# STM32WLE5CBU6_dev_board.net
KiCad netlist of a schematic drawn in Altium Designer
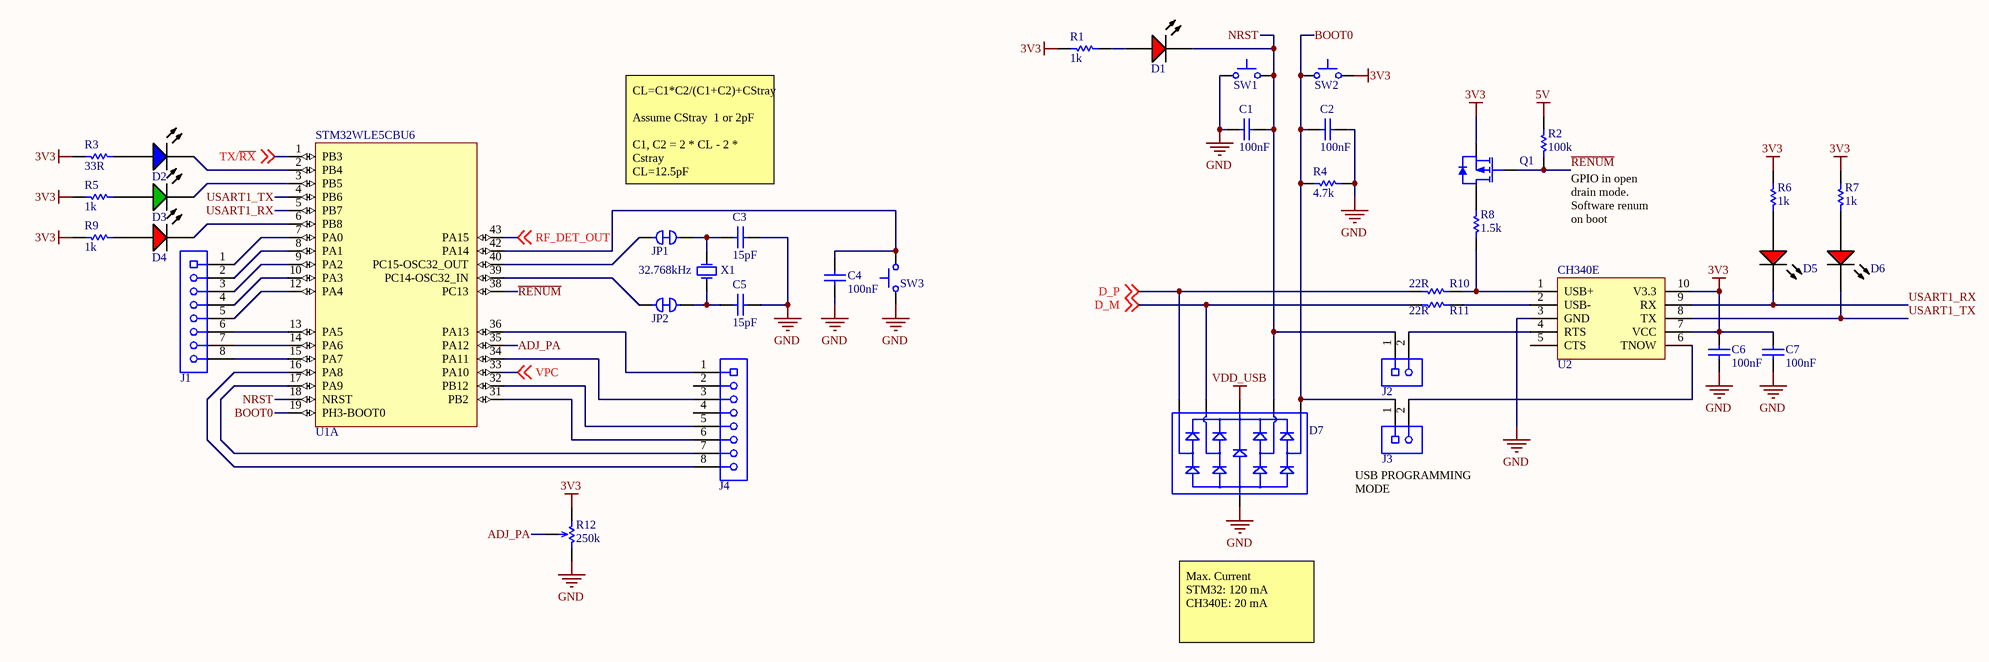
[diagram p0: STM32WLE5CBU6 dev board.SchDoc]

(export (version "E")
  (design (tool "Eeschema 10.0.6"))
  (components
    (comp (ref "C1")
      (value "100nF")
      (footprint "CAPC1608X10N")
      (description "Cap Ceramic 0.1uF 50V X7R 20% SMD 0603 125C T/R")
      (fields (field (name "TOLERANCE") "20%") (field (name "Comment") "C0603C104M5RACTU"))
      (libsource (lib "UWA Aerospace") (part "C0603C104M5RACTU"))
    )
    (comp (ref "C2")
      (value "100nF")
      (footprint "CAPC1608X10N")
      (description "Cap Ceramic 0.1uF 50V X7R 20% SMD 0603 125C T/R")
      (fields (field (name "TOLERANCE") "20%") (field (name "Comment") "C0603C104M5RACTU"))
      (libsource (lib "UWA Aerospace") (part "C0603C104M5RACTU"))
    )
    (comp (ref "C3")
      (value "15pF")
      (footprint "CAPC1005X05N")
      (description "CAP CER 15PF 50V C0G/NP0 0402")
      (fields (field (name "VOLTAGE") "50V") (field (name "TOLERANCE") "5%"))
      (libsource (lib "UWA Aerospace") (part "C0603C104M5RACTU"))
    )
    (comp (ref "C4")
      (value "100nF")
      (footprint "CAPC1608X10N")
      (description "Cap Ceramic 0.1uF 50V X7R 20% SMD 0603 125C T/R")
      (fields (field (name "TOLERANCE") "20%") (field (name "Comment") "C0603C104M5RACTU"))
      (libsource (lib "UWA Aerospace") (part "C0603C104M5RACTU"))
    )
    (comp (ref "C5")
      (value "15pF")
      (footprint "CAPC1005X05N")
      (description "CAP CER 15PF 50V C0G/NP0 0402")
      (fields (field (name "VOLTAGE") "50V") (field (name "TOLERANCE") "5%"))
      (libsource (lib "UWA Aerospace") (part "C0603C104M5RACTU"))
    )
    (comp (ref "C6")
      (value "100nF")
      (footprint "CAPC1608X10N")
      (description "Cap Ceramic 0.1uF 50V X7R 20% SMD 0603 125C T/R")
      (fields (field (name "TOLERANCE") "20%") (field (name "Comment") "C0603C104M5RACTU"))
      (libsource (lib "UWA Aerospace") (part "C0603C104M5RACTU"))
    )
    (comp (ref "C7")
      (value "100nF")
      (footprint "CAPC1608X10N")
      (description "Cap Ceramic 0.1uF 50V X7R 20% SMD 0603 125C T/R")
      (fields (field (name "TOLERANCE") "20%") (field (name "Comment") "C0603C104M5RACTU"))
      (libsource (lib "UWA Aerospace") (part "C0603C104M5RACTU"))
    )
    (comp (ref "D1")
      (value "150060RS75000")
      (footprint "0603_A")
      (description "LED Low-Power Uni-Color Red 630nm 2V 2-Pin Chip 0603(1608Metric) T/R")
      (libsource (lib "UWA Aerospace") (part "LED - Red"))
    )
    (comp (ref "D2")
      (value "LTST-C191TBKT")
      (footprint "FP-150060GS75000-MFG")
      (description "LED BLUE CLEAR 0603 SMD")
      (libsource (lib "UWA Aerospace") (part "LED - Blue"))
    )
    (comp (ref "D3")
      (value "150060GS75000")
      (footprint "FP-150060GS75000-MFG")
      (description "Led, Green, 520 Nm, 3.2 V, 30 Ma, 430 Mcd Rohs Compliant: Yes")
      (libsource (lib "UWA Aerospace") (part "LED - Green"))
    )
    (comp (ref "D4")
      (value "150060RS75000")
      (footprint "0603_A")
      (description "LED Low-Power Uni-Color Red 630nm 2V 2-Pin Chip 0603(1608Metric) T/R")
      (libsource (lib "UWA Aerospace") (part "LED - Red"))
    )
    (comp (ref "D5")
      (value "150060RS75000")
      (footprint "0603_A")
      (description "LED Low-Power Uni-Color Red 630nm 2V 2-Pin Chip 0603(1608Metric) T/R")
      (libsource (lib "UWA Aerospace") (part "LED - Red"))
    )
    (comp (ref "D6")
      (value "150060RS75000")
      (footprint "0603_A")
      (description "LED Low-Power Uni-Color Red 630nm 2V 2-Pin Chip 0603(1608Metric) T/R")
      (libsource (lib "UWA Aerospace") (part "LED - Red"))
    )
    (comp (ref "D7")
      (value "SRV05-4-P-T7")
      (footprint "SOT95P280X145-6N")
      (description "SRV05 Series 4 Ch 3.5 pF 15 Vclamp Steering Diode/TVS Array Combo - SOT-23-6 USB ESD")
      (libsource (lib "UWA Aerospace") (part "Diode - USB Clamp (Dual USB)"))
    )
    (comp (ref "J1")
      (value "22-28-4080")
      (footprint "22-28-4080-Footprint-1")
      (description "Conn Unshrouded Header HDR 8 POS 2.54mm Solder ST Thru-Hole Bag")
      (libsource (lib "") (part "Connector - 1x8 Single Sided_1"))
    )
    (comp (ref "J2")
      (value "22-28-4020")
      (footprint "22-28-4020-Footprint-1")
      (description "KK 254 Breakaway Header, Vertical, 2 Circuits, Tin (Sn) Plating, Mating Pin Length 6.09mm 2 POS")
      (libsource (lib "UWA Aerospace") (part "22-28-4020"))
    )
    (comp (ref "J3")
      (value "22-28-4020")
      (footprint "22-28-4020-Footprint-1")
      (description "KK 254 Breakaway Header, Vertical, 2 Circuits, Tin (Sn) Plating, Mating Pin Length 6.09mm 2 POS")
      (libsource (lib "UWA Aerospace") (part "22-28-4020"))
    )
    (comp (ref "J4")
      (value "22-28-4080")
      (footprint "22-28-4080-Footprint-1")
      (description "Conn Unshrouded Header HDR 8 POS 2.54mm Solder ST Thru-Hole Bag")
      (libsource (lib "UWA Aerospace") (part "Connector - 1x8 Single Sided"))
    )
    (comp (ref "JP1")
      (value "RC0603FR-070RL")
      (footprint "RESC1608X05N")
      (description "RC Series 0603 0.1 W 0 Ohm Jumper Surface Mount Thick Film Chip Resistor")
      (fields (field (name "TOLERANCE") "1%"))
      (libsource (lib "UWA Aerospace") (part "Jumper - Closed"))
    )
    (comp (ref "JP2")
      (value "RC0603FR-070RL")
      (footprint "RESC1608X05N")
      (description "RC Series 0603 0.1 W 0 Ohm Jumper Surface Mount Thick Film Chip Resistor")
      (fields (field (name "TOLERANCE") "1%"))
      (libsource (lib "UWA Aerospace") (part "Jumper - Closed"))
    )
    (comp (ref "Q1")
      (value "SI2301CDS-T1-GE3")
      (footprint "SOT95P237X112-3N")
      (description "Trans Mosfet P-ch 20V 3.1A 3-PIN SOT-23 T/r / Mosfet P-ch 20V 3.1A SOT23-3")
      (libsource (lib "UWA Aerospace") (part "Transistor - MOSFET P-Channel"))
    )
    (comp (ref "R1")
      (value "1k")
      (footprint "RESC1608X05N")
      (description "Res Thick Film 0603 1K Ohm 1% 1/10W ±100ppm/°C Molded SMD SMD Paper T/R")
      (fields (field (name "TOLERANCE") "1%") (field (name "Comment") "RC0603FR-071KL"))
      (libsource (lib "UWA Aerospace") (part "Resistor"))
    )
    (comp (ref "R2")
      (value "100k")
      (footprint "RESC1608X05N")
      (description "RES SMD 100K OHM 1% 1/10W 0603")
      (fields (field (name "TOLERANCE") "1%") (field (name "Comment") "RC0603FR-07100KL"))
      (libsource (lib "UWA Aerospace") (part "Resistor"))
    )
    (comp (ref "R3")
      (value "33R")
      (footprint "RESC1608X05N")
      (description "Res Thick Film 0603 33 Ohm 1% 1/10W ±100ppm/°C Molded SMD Paper T/R")
      (fields (field (name "TOLERANCE") "1%") (field (name "Comment") "CRCW060333R0FKEAC"))
      (libsource (lib "UWA Aerospace") (part "Resistor"))
    )
    (comp (ref "R4")
      (value "CRCW06034K70FKEAC")
      (footprint "RESC1608X05N")
      (description "4.7kO 1% 0603 thick film")
      (fields (field (name "RESISTANCE") "4.7k") (field (name "TOLERANCE") "1%"))
      (libsource (lib "UWA Aerospace") (part "WSL2010R0100FEA18"))
    )
    (comp (ref "R5")
      (value "1k")
      (footprint "RESC1608X05N")
      (description "Res Thick Film 0603 1K Ohm 1% 1/10W ±100ppm/°C Molded SMD SMD Paper T/R")
      (fields (field (name "TOLERANCE") "1%") (field (name "Comment") "RC0603FR-071KL"))
      (libsource (lib "UWA Aerospace") (part "Resistor"))
    )
    (comp (ref "R6")
      (value "1k")
      (footprint "RESC1608X05N")
      (description "Res Thick Film 0603 1K Ohm 1% 1/10W ±100ppm/°C Molded SMD SMD Paper T/R")
      (fields (field (name "TOLERANCE") "1%") (field (name "Comment") "RC0603FR-071KL"))
      (libsource (lib "UWA Aerospace") (part "Resistor"))
    )
    (comp (ref "R7")
      (value "1k")
      (footprint "RESC1608X05N")
      (description "Res Thick Film 0603 1K Ohm 1% 1/10W ±100ppm/°C Molded SMD SMD Paper T/R")
      (fields (field (name "TOLERANCE") "1%") (field (name "Comment") "RC0603FR-071KL"))
      (libsource (lib "UWA Aerospace") (part "Resistor"))
    )
    (comp (ref "R8")
      (value "1.5k")
      (footprint "RESC1608X05N")
      (description "Res Thick Film 0603 1.5K Ohm 5% 0.1W(1/10W) ±200ppm/C Pad SMD Automotive T/R")
      (fields (field (name "TOLERANCE") "5%") (field (name "Comment") "RK73B1JTTD152J"))
      (libsource (lib "UWA Aerospace") (part "Resistor"))
    )
    (comp (ref "R9")
      (value "1k")
      (footprint "RESC1608X05N")
      (description "Res Thick Film 0603 1K Ohm 1% 1/10W ±100ppm/°C Molded SMD SMD Paper T/R")
      (fields (field (name "TOLERANCE") "1%") (field (name "Comment") "RC0603FR-071KL"))
      (libsource (lib "UWA Aerospace") (part "Resistor"))
    )
    (comp (ref "R10")
      (value "22R")
      (footprint "RESC1005X04N")
      (description "22R 1/16W %1 0402")
      (fields (field (name "TOLERANCE") "±1%") (field (name "Comment") "0402WGF220JTCE"))
      (libsource (lib "UWA Aerospace") (part "Resistor"))
    )
    (comp (ref "R11")
      (value "22R")
      (footprint "RESC1005X04N")
      (description "22R 1/16W %1 0402")
      (fields (field (name "TOLERANCE") "±1%") (field (name "Comment") "0402WGF220JTCE"))
      (libsource (lib "UWA Aerospace") (part "Resistor"))
    )
    (comp (ref "R12")
      (value "250k")
      (footprint "3362P-1-502LF-Footprint-1")
      (description "Bourns 3362P-1-254LF THT Trimpot, 250k, 10%, 1 Turn")
      (fields (field (name "TOLERANCE") "10%") (field (name "Comment") "3362P-1-254LF"))
      (libsource (lib "UWA Aerospace") (part "3362F-1-254LF"))
    )
    (comp (ref "SW1")
      (value "TL3342F160QG")
      (footprint "ESWI-TL3342F160QG_V")
      (description "Switch Tactile N.O. SPST Round Button Gull Wing 0.05A 12VDC 100000Cycles 1.57N SMD T/R")
      (libsource (lib "UWA Aerospace") (part "Switch - Tactile"))
    )
    (comp (ref "SW2")
      (value "TL3342F160QG")
      (footprint "ESWI-TL3342F160QG_V")
      (description "Switch Tactile N.O. SPST Round Button Gull Wing 0.05A 12VDC 100000Cycles 1.57N SMD T/R")
      (libsource (lib "UWA Aerospace") (part "Switch - Tactile"))
    )
    (comp (ref "SW3")
      (value "TL3342F160QG")
      (footprint "ESWI-TL3342F160QG_V")
      (description "Switch Tactile N.O. SPST Round Button Gull Wing 0.05A 12VDC 100000Cycles 1.57N SMD T/R")
      (libsource (lib "UWA Aerospace") (part "Switch - Tactile"))
    )
    (comp (ref "U1")
      (value "STM32WLE5CBU6")
      (footprint "QFN50P700X700X60_HS-49L")
      (description "Microcontroller 32-Bit Arm Cortex-M4 RISC 128Kbyte 1.8V to 3.6V 48-Pin UFQFPN Industrial")
      (libsource (lib "UWA Aerospace") (part "STM32WLE5CBU6-Symbol-1"))
    )
    (comp (ref "U2")
      (value "CH340E")
      (footprint "TSSOP50P490X110-10N")
      (description "Transceiver 2Mbps USB 2.0 MSOP-10 USB ICs ROHS")
      (libsource (lib "UWA Aerospace") (part "CH340-Symbol-1"))
    )
    (comp (ref "X1")
      (value "32.768kHz")
      (footprint "Q13FC1350000400-Footprint-1")
      (description "Crystal 0.032768MHz ±20ppm (Tol) 12.5pF FUND 70000Ohm 2-Pin CSMD T/R 32.768 kHz")
      (fields (field (name "Comment") "Q13FC1350000400"))
      (libsource (lib "UWA Aerospace") (part "Crystal"))
    )
  )
  (nets
    (net (code "1") (name "/ADJ_PA") (class "Default")
      (node (ref "R12") (pin "2") (pinfunction "W_2") (pintype "passive"))
      (node (ref "U1") (pin "35") (pinfunction "PA12_35") (pintype "bidirectional"))
    )
    (net (code "2") (name "/BOOT0") (class "Default")
      (node (ref "C2") (pin "2") (pinfunction "2_2") (pintype "passive"))
      (node (ref "D7") (pin "6") (pinfunction "6_6") (pintype "passive"))
      (node (ref "J3") (pin "1") (pinfunction "1_1") (pintype "passive"))
      (node (ref "R4") (pin "2") (pinfunction "2_2") (pintype "passive"))
      (node (ref "SW2") (pin "1") (pinfunction "1_1") (pintype "passive"))
      (node (ref "U1") (pin "19") (pinfunction "PH3-BOOT0_19") (pintype "bidirectional"))
    )
    (net (code "3") (name "/NRST") (class "Default")
      (node (ref "C1") (pin "1") (pinfunction "1_1") (pintype "passive"))
      (node (ref "D1") (pin "2") (pinfunction "K_2") (pintype "passive"))
      (node (ref "D7") (pin "4") (pinfunction "4_4") (pintype "passive"))
      (node (ref "J2") (pin "1") (pinfunction "1_1") (pintype "passive"))
      (node (ref "SW1") (pin "2") (pinfunction "2_2") (pintype "passive"))
      (node (ref "U1") (pin "18") (pinfunction "NRST_18") (pintype "bidirectional"))
    )
    (net (code "4") (name "/USART1_RX") (class "Default")
      (node (ref "D5") (pin "2") (pinfunction "K_2") (pintype "passive"))
      (node (ref "U1") (pin "5") (pinfunction "PB7_5") (pintype "bidirectional"))
      (node (ref "U2") (pin "9") (pinfunction "RX_9") (pintype "passive"))
    )
    (net (code "5") (name "/USART1_TX") (class "Default")
      (node (ref "D6") (pin "2") (pinfunction "K_2") (pintype "passive"))
      (node (ref "U1") (pin "4") (pinfunction "PB6_4") (pintype "bidirectional"))
      (node (ref "U2") (pin "8") (pinfunction "TX_8") (pintype "passive"))
    )
    (net (code "6") (name "/~{RENUM}") (class "Default")
      (node (ref "Q1") (pin "1") (pinfunction "G_1") (pintype "passive"))
      (node (ref "R2") (pin "1") (pinfunction "1_1") (pintype "passive"))
      (node (ref "U1") (pin "38") (pinfunction "PC13_38") (pintype "bidirectional"))
    )
    (net (code "7") (name "3V3") (class "Default")
      (node (ref "C6") (pin "2") (pinfunction "2_2") (pintype "passive"))
      (node (ref "C7") (pin "2") (pinfunction "2_2") (pintype "passive"))
      (node (ref "Q1") (pin "2") (pinfunction "S_2") (pintype "passive"))
      (node (ref "R1") (pin "2") (pinfunction "2_2") (pintype "passive"))
      (node (ref "R12") (pin "1") (pinfunction "CCW_1") (pintype "passive"))
      (node (ref "R3") (pin "1") (pinfunction "1_1") (pintype "passive"))
      (node (ref "R5") (pin "2") (pinfunction "2_2") (pintype "passive"))
      (node (ref "R6") (pin "2") (pinfunction "2_2") (pintype "passive"))
      (node (ref "R7") (pin "2") (pinfunction "2_2") (pintype "passive"))
      (node (ref "R9") (pin "2") (pinfunction "2_2") (pintype "passive"))
      (node (ref "SW2") (pin "2") (pinfunction "2_2") (pintype "passive"))
      (node (ref "U2") (pin "10") (pinfunction "V3.3_10") (pintype "passive"))
      (node (ref "U2") (pin "7") (pinfunction "VCC_7") (pintype "passive"))
    )
    (net (code "8") (name "5V") (class "Default")
      (node (ref "R2") (pin "2") (pinfunction "2_2") (pintype "passive"))
    )
    (net (code "9") (name "D_M") (class "Default")
      (node (ref "D7") (pin "3") (pinfunction "3_3") (pintype "passive"))
      (node (ref "R11") (pin "1") (pinfunction "1_1") (pintype "passive"))
    )
    (net (code "10") (name "D_P") (class "Default")
      (node (ref "D7") (pin "1") (pinfunction "1_1") (pintype "passive"))
      (node (ref "R10") (pin "1") (pinfunction "1_1") (pintype "passive"))
    )
    (net (code "11") (name "GND") (class "Default")
      (node (ref "C1") (pin "2") (pinfunction "2_2") (pintype "passive"))
      (node (ref "C2") (pin "1") (pinfunction "1_1") (pintype "passive"))
      (node (ref "C3") (pin "1") (pinfunction "1_1") (pintype "passive"))
      (node (ref "C4") (pin "2") (pinfunction "2_2") (pintype "passive"))
      (node (ref "C5") (pin "1") (pinfunction "1_1") (pintype "passive"))
      (node (ref "C6") (pin "1") (pinfunction "1_1") (pintype "passive"))
      (node (ref "C7") (pin "1") (pinfunction "1_1") (pintype "passive"))
      (node (ref "D7") (pin "2") (pinfunction "2_2") (pintype "passive"))
      (node (ref "R12") (pin "3") (pinfunction "CW_3") (pintype "passive"))
      (node (ref "R4") (pin "1") (pinfunction "1_1") (pintype "passive"))
      (node (ref "SW1") (pin "1") (pinfunction "1_1") (pintype "passive"))
      (node (ref "SW3") (pin "1") (pinfunction "1_1") (pintype "passive"))
      (node (ref "U2") (pin "3") (pinfunction "GND_3") (pintype "passive"))
    )
    (net (code "12") (name "Net-(D1-A)") (class "Default")
      (node (ref "D1") (pin "1") (pinfunction "A_1") (pintype "passive"))
      (node (ref "R1") (pin "1") (pinfunction "1_1") (pintype "passive"))
    )
    (net (code "13") (name "Net-(D2-A)") (class "Default")
      (node (ref "D2") (pin "1") (pinfunction "A_1") (pintype "passive"))
      (node (ref "R3") (pin "2") (pinfunction "2_2") (pintype "passive"))
    )
    (net (code "14") (name "Net-(D2-K)") (class "Default")
      (node (ref "D2") (pin "2") (pinfunction "K_2") (pintype "passive"))
      (node (ref "U1") (pin "2") (pinfunction "PB4_2") (pintype "bidirectional"))
    )
    (net (code "15") (name "Net-(D3-A)") (class "Default")
      (node (ref "D3") (pin "1") (pinfunction "A_1") (pintype "passive"))
      (node (ref "R5") (pin "1") (pinfunction "1_1") (pintype "passive"))
    )
    (net (code "16") (name "Net-(D3-K)") (class "Default")
      (node (ref "D3") (pin "2") (pinfunction "K_2") (pintype "passive"))
      (node (ref "U1") (pin "3") (pinfunction "PB5_3") (pintype "bidirectional"))
    )
    (net (code "17") (name "Net-(D4-A)") (class "Default")
      (node (ref "D4") (pin "1") (pinfunction "A_1") (pintype "passive"))
      (node (ref "R9") (pin "1") (pinfunction "1_1") (pintype "passive"))
    )
    (net (code "18") (name "Net-(D4-K)") (class "Default")
      (node (ref "D4") (pin "2") (pinfunction "K_2") (pintype "passive"))
      (node (ref "U1") (pin "6") (pinfunction "PB8_6") (pintype "bidirectional"))
    )
    (net (code "19") (name "Net-(D5-A)") (class "Default")
      (node (ref "D5") (pin "1") (pinfunction "A_1") (pintype "passive"))
      (node (ref "R6") (pin "1") (pinfunction "1_1") (pintype "passive"))
    )
    (net (code "20") (name "Net-(D6-A)") (class "Default")
      (node (ref "D6") (pin "1") (pinfunction "A_1") (pintype "passive"))
      (node (ref "R7") (pin "1") (pinfunction "1_1") (pintype "passive"))
    )
    (net (code "21") (name "Net-(Q1-D)") (class "Default")
      (node (ref "Q1") (pin "3") (pinfunction "D_3") (pintype "passive"))
      (node (ref "R8") (pin "2") (pinfunction "2_2") (pintype "passive"))
    )
    (net (code "22") (name "Net-(U1A-PA0)") (class "Default")
      (node (ref "J1") (pin "1") (pinfunction "1_1") (pintype "passive"))
      (node (ref "U1") (pin "7") (pinfunction "PA0_7") (pintype "bidirectional"))
    )
    (net (code "23") (name "Net-(U1A-PA1)") (class "Default")
      (node (ref "J1") (pin "2") (pinfunction "2_2") (pintype "passive"))
      (node (ref "U1") (pin "8") (pinfunction "PA1_8") (pintype "bidirectional"))
    )
    (net (code "24") (name "Net-(U1A-PA2)") (class "Default")
      (node (ref "J1") (pin "3") (pinfunction "3_3") (pintype "passive"))
      (node (ref "U1") (pin "9") (pinfunction "PA2_9") (pintype "bidirectional"))
    )
    (net (code "25") (name "Net-(U1A-PA3)") (class "Default")
      (node (ref "J1") (pin "4") (pinfunction "4_4") (pintype "passive"))
      (node (ref "U1") (pin "10") (pinfunction "PA3_10") (pintype "bidirectional"))
    )
    (net (code "26") (name "Net-(U1A-PA4)") (class "Default")
      (node (ref "J1") (pin "5") (pinfunction "5_5") (pintype "passive"))
      (node (ref "U1") (pin "12") (pinfunction "PA4_12") (pintype "bidirectional"))
    )
    (net (code "27") (name "Net-(U1A-PA5)") (class "Default")
      (node (ref "J1") (pin "6") (pinfunction "6_6") (pintype "passive"))
      (node (ref "U1") (pin "13") (pinfunction "PA5_13") (pintype "bidirectional"))
    )
    (net (code "28") (name "Net-(U1A-PA6)") (class "Default")
      (node (ref "J1") (pin "7") (pinfunction "7_7") (pintype "passive"))
      (node (ref "U1") (pin "14") (pinfunction "PA6_14") (pintype "bidirectional"))
    )
    (net (code "29") (name "Net-(U1A-PA7)") (class "Default")
      (node (ref "J1") (pin "8") (pinfunction "8_8") (pintype "passive"))
      (node (ref "U1") (pin "15") (pinfunction "PA7_15") (pintype "bidirectional"))
    )
    (net (code "30") (name "Net-(U1A-PA8)") (class "Default")
      (node (ref "J4") (pin "8") (pinfunction "8_8") (pintype "passive"))
      (node (ref "U1") (pin "16") (pinfunction "PA8_16") (pintype "bidirectional"))
    )
    (net (code "31") (name "Net-(U1A-PA9)") (class "Default")
      (node (ref "J4") (pin "7") (pinfunction "7_7") (pintype "passive"))
      (node (ref "U1") (pin "17") (pinfunction "PA9_17") (pintype "bidirectional"))
    )
    (net (code "32") (name "Net-(U1A-PA11)") (class "Default")
      (node (ref "J4") (pin "3") (pinfunction "3_3") (pintype "passive"))
      (node (ref "U1") (pin "34") (pinfunction "PA11_34") (pintype "bidirectional"))
    )
    (net (code "33") (name "Net-(U1A-PA13)") (class "Default")
      (node (ref "J4") (pin "1") (pinfunction "1_1") (pintype "passive"))
      (node (ref "U1") (pin "36") (pinfunction "PA13_36") (pintype "bidirectional"))
    )
    (net (code "34") (name "Net-(U1A-PA14)") (class "Default")
      (node (ref "C4") (pin "1") (pinfunction "1_1") (pintype "passive"))
      (node (ref "SW3") (pin "2") (pinfunction "2_2") (pintype "passive"))
      (node (ref "U1") (pin "42") (pinfunction "PA14_42") (pintype "bidirectional"))
    )
    (net (code "35") (name "Net-(U1A-PB2)") (class "Default")
      (node (ref "J4") (pin "6") (pinfunction "6_6") (pintype "passive"))
      (node (ref "U1") (pin "31") (pinfunction "PB2_31") (pintype "bidirectional"))
    )
    (net (code "36") (name "Net-(U1A-PB12)") (class "Default")
      (node (ref "J4") (pin "5") (pinfunction "5_5") (pintype "passive"))
      (node (ref "U1") (pin "32") (pinfunction "PB12_32") (pintype "bidirectional"))
    )
    (net (code "37") (name "Net-(U1A-PC14-OSC32_IN)") (class "Default")
      (node (ref "JP2") (pin "1") (pinfunction "1_1") (pintype "passive"))
      (node (ref "U1") (pin "39") (pinfunction "PC14-OSC32_IN_39") (pintype "bidirectional"))
    )
    (net (code "38") (name "Net-(U1A-PC15-OSC32_OUT)") (class "Default")
      (node (ref "JP1") (pin "1") (pinfunction "1_1") (pintype "passive"))
      (node (ref "U1") (pin "40") (pinfunction "PC15-OSC32_OUT_40") (pintype "bidirectional"))
    )
    (net (code "39") (name "Net-(U2-RTS)") (class "Default")
      (node (ref "J2") (pin "2") (pinfunction "2_2") (pintype "passive"))
      (node (ref "U2") (pin "4") (pinfunction "RTS_4") (pintype "passive"))
    )
    (net (code "40") (name "Net-(U2-TNOW)") (class "Default")
      (node (ref "J3") (pin "2") (pinfunction "2_2") (pintype "passive"))
      (node (ref "U2") (pin "6") (pinfunction "TNOW_6") (pintype "passive"))
    )
    (net (code "41") (name "Net-(U2-USB+)") (class "Default")
      (node (ref "R10") (pin "2") (pinfunction "2_2") (pintype "passive"))
      (node (ref "R8") (pin "1") (pinfunction "1_1") (pintype "passive"))
      (node (ref "U2") (pin "1") (pinfunction "USB+_1") (pintype "passive"))
    )
    (net (code "42") (name "Net-(U2-USB-)") (class "Default")
      (node (ref "R11") (pin "2") (pinfunction "2_2") (pintype "passive"))
      (node (ref "U2") (pin "2") (pinfunction "USB-_2") (pintype "passive"))
    )
    (net (code "43") (name "Net-(X1-OSC1)") (class "Default")
      (node (ref "C5") (pin "2") (pinfunction "2_2") (pintype "passive"))
      (node (ref "JP2") (pin "2") (pinfunction "2_2") (pintype "passive"))
      (node (ref "X1") (pin "1") (pinfunction "OSC1_1") (pintype "passive"))
    )
    (net (code "44") (name "Net-(X1-OSC2)") (class "Default")
      (node (ref "C3") (pin "2") (pinfunction "2_2") (pintype "passive"))
      (node (ref "JP1") (pin "2") (pinfunction "2_2") (pintype "passive"))
      (node (ref "X1") (pin "2") (pinfunction "OSC2_2") (pintype "passive"))
    )
    (net (code "45") (name "RF_DET_OUT") (class "Default")
      (node (ref "U1") (pin "43") (pinfunction "PA15_43") (pintype "bidirectional"))
    )
    (net (code "46") (name "TX{slash}~{RX}") (class "Default")
      (node (ref "U1") (pin "1") (pinfunction "PB3_1") (pintype "bidirectional"))
    )
    (net (code "47") (name "VDD_USB") (class "Default")
      (node (ref "D7") (pin "5") (pinfunction "5_5") (pintype "passive"))
    )
    (net (code "48") (name "VPC") (class "Default")
      (node (ref "U1") (pin "33") (pinfunction "PA10_33") (pintype "bidirectional"))
    )
    (net (code "49") (name "unconnected-(J4-Pad2)") (class "Default")
      (node (ref "J4") (pin "2") (pinfunction "2_2") (pintype "passive"))
    )
    (net (code "50") (name "unconnected-(J4-Pad4)") (class "Default")
      (node (ref "J4") (pin "4") (pinfunction "4_4") (pintype "passive"))
    )
    (net (code "51") (name "unconnected-(U2-CTS-Pad5)") (class "Default")
      (node (ref "U2") (pin "5") (pinfunction "CTS_5") (pintype "passive"))
    )
  )
)
